# pedalboard.net
KiCad netlist of a schematic drawn in EAGLE
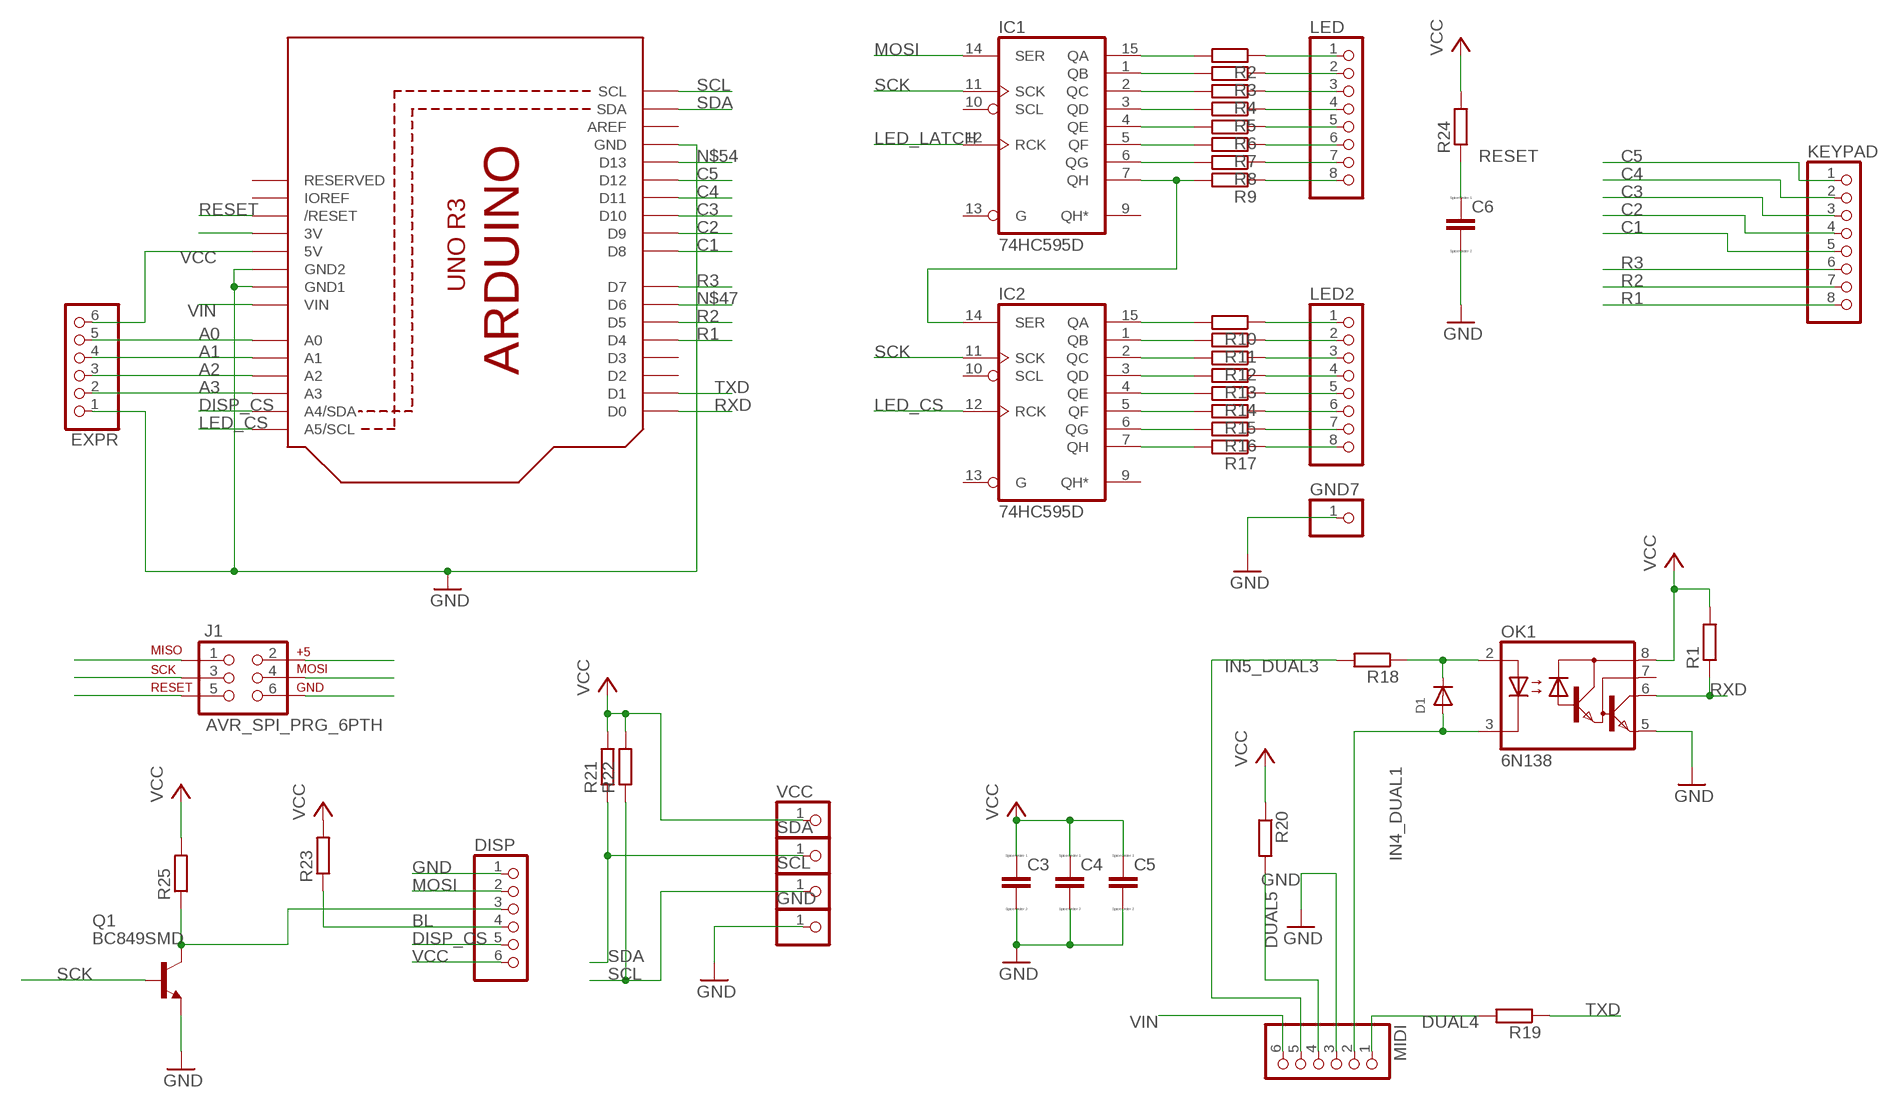
[diagram p0: schematic, sheet 1]

(export (version "E")
  (design (tool "Eeschema 10.0.6"))
  (components
    (comp (ref "C3")
      (value "CC0603")
      (footprint "eagle-import:C0603")
      (libsource (lib "eagle-import") (part "CC0603"))
    )
    (comp (ref "C4")
      (value "CC0603")
      (footprint "eagle-import:C0603")
      (libsource (lib "eagle-import") (part "CC0603"))
    )
    (comp (ref "C5") (value "C") (footprint "eagle-import:C0805") (libsource (lib "eagle-import") (part "C")))
    (comp (ref "C6")
      (value "CC0603")
      (footprint "eagle-import:C0603")
      (libsource (lib "eagle-import") (part "CC0603"))
    )
    (comp (ref "D1")
      (value "DIODEDO-1N4148")
      (footprint "eagle-import:DO-1N4148")
      (libsource (lib "eagle-import") (part "DIODEDO-1N4148"))
    )
    (comp (ref "DISP")
      (value "PINHD-1X6")
      (footprint "eagle-import:1X06")
      (libsource (lib "eagle-import") (part "PINHD-1X6"))
    )
    (comp (ref "EXPR")
      (value "PINHD-1X6")
      (footprint "eagle-import:1X06")
      (libsource (lib "eagle-import") (part "PINHD-1X6"))
    )
    (comp (ref "GND")
      (value "PINHD-1X1")
      (footprint "eagle-import:1X01")
      (libsource (lib "eagle-import") (part "PINHD-1X1"))
    )
    (comp (ref "GND7")
      (value "PINHD-1X1")
      (footprint "eagle-import:1X01")
      (libsource (lib "eagle-import") (part "PINHD-1X1"))
    )
    (comp (ref "IC1")
      (value "74HC595D")
      (footprint "eagle-import:SO16")
      (libsource (lib "eagle-import") (part "74595DHC"))
    )
    (comp (ref "IC2")
      (value "74HC595D")
      (footprint "eagle-import:SO16")
      (libsource (lib "eagle-import") (part "74595DHC"))
    )
    (comp (ref "J1")
      (value "AVR_SPI_PRG_6PTH")
      (footprint "eagle-import:2X3")
      (libsource (lib "eagle-import") (part "AVR_SPI_PRG_6PTH"))
    )
    (comp (ref "KEYPAD")
      (value "PINHD-1X8CLEANBIG")
      (footprint "eagle-import:1X08-CLEANBIG")
      (libsource (lib "eagle-import") (part "PINHD-1X8CLEANBIG"))
    )
    (comp (ref "LED")
      (value "PINHD-1X8CLEANBIG")
      (footprint "eagle-import:1X08-CLEANBIG")
      (libsource (lib "eagle-import") (part "PINHD-1X8CLEANBIG"))
    )
    (comp (ref "LED2")
      (value "PINHD-1X8CLEANBIG")
      (footprint "eagle-import:1X08-CLEANBIG")
      (libsource (lib "eagle-import") (part "PINHD-1X8CLEANBIG"))
    )
    (comp (ref "MIDI")
      (value "PINHD-1X6")
      (footprint "eagle-import:1X06")
      (libsource (lib "eagle-import") (part "PINHD-1X6"))
    )
    (comp (ref "OK1")
      (value "6N138")
      (footprint "eagle-import:DIL08")
      (fields (field (name "MF") "VISHAY/TELEFUNKEN"))
      (libsource (lib "eagle-import") (part "6N138"))
    )
    (comp (ref "Q1")
      (value "BC849SMD")
      (footprint "eagle-import:SOT23-BEC")
      (libsource (lib "eagle-import") (part "BC849SMD"))
    )
    (comp (ref "R1")
      (value "R-EU_R0805")
      (footprint "eagle-import:R0805")
      (libsource (lib "eagle-import") (part "R-EU_R0805"))
    )
    (comp (ref "R2")
      (value "R-EU_R0805")
      (footprint "eagle-import:R0805")
      (libsource (lib "eagle-import") (part "R-EU_R0805"))
    )
    (comp (ref "R3")
      (value "R-EU_R0805")
      (footprint "eagle-import:R0805")
      (libsource (lib "eagle-import") (part "R-EU_R0805"))
    )
    (comp (ref "R4")
      (value "R-EU_R0805")
      (footprint "eagle-import:R0805")
      (libsource (lib "eagle-import") (part "R-EU_R0805"))
    )
    (comp (ref "R5")
      (value "R-EU_R0805")
      (footprint "eagle-import:R0805")
      (libsource (lib "eagle-import") (part "R-EU_R0805"))
    )
    (comp (ref "R6")
      (value "R-EU_R0805")
      (footprint "eagle-import:R0805")
      (libsource (lib "eagle-import") (part "R-EU_R0805"))
    )
    (comp (ref "R7")
      (value "R-EU_R0805")
      (footprint "eagle-import:R0805")
      (libsource (lib "eagle-import") (part "R-EU_R0805"))
    )
    (comp (ref "R8")
      (value "R-EU_R0805")
      (footprint "eagle-import:R0805")
      (libsource (lib "eagle-import") (part "R-EU_R0805"))
    )
    (comp (ref "R9")
      (value "R-EU_R0805")
      (footprint "eagle-import:R0805")
      (libsource (lib "eagle-import") (part "R-EU_R0805"))
    )
    (comp (ref "R10")
      (value "R-EU_R0805")
      (footprint "eagle-import:R0805")
      (libsource (lib "eagle-import") (part "R-EU_R0805"))
    )
    (comp (ref "R11")
      (value "R-EU_R0805")
      (footprint "eagle-import:R0805")
      (libsource (lib "eagle-import") (part "R-EU_R0805"))
    )
    (comp (ref "R12")
      (value "R-EU_R0805")
      (footprint "eagle-import:R0805")
      (libsource (lib "eagle-import") (part "R-EU_R0805"))
    )
    (comp (ref "R13")
      (value "R-EU_R0805")
      (footprint "eagle-import:R0805")
      (libsource (lib "eagle-import") (part "R-EU_R0805"))
    )
    (comp (ref "R14")
      (value "R-EU_R0805")
      (footprint "eagle-import:R0805")
      (libsource (lib "eagle-import") (part "R-EU_R0805"))
    )
    (comp (ref "R15")
      (value "R-EU_R0805")
      (footprint "eagle-import:R0805")
      (libsource (lib "eagle-import") (part "R-EU_R0805"))
    )
    (comp (ref "R16")
      (value "R-EU_R0805")
      (footprint "eagle-import:R0805")
      (libsource (lib "eagle-import") (part "R-EU_R0805"))
    )
    (comp (ref "R17")
      (value "R-EU_R0805")
      (footprint "eagle-import:R0805")
      (libsource (lib "eagle-import") (part "R-EU_R0805"))
    )
    (comp (ref "R18")
      (value "R-EU_R0805")
      (footprint "eagle-import:R0805")
      (libsource (lib "eagle-import") (part "R-EU_R0805"))
    )
    (comp (ref "R19")
      (value "R-EU_R0805")
      (footprint "eagle-import:R0805")
      (libsource (lib "eagle-import") (part "R-EU_R0805"))
    )
    (comp (ref "R20")
      (value "R-EU_R0805")
      (footprint "eagle-import:R0805")
      (libsource (lib "eagle-import") (part "R-EU_R0805"))
    )
    (comp (ref "R21")
      (value "R-EU_R0805")
      (footprint "eagle-import:R0805")
      (libsource (lib "eagle-import") (part "R-EU_R0805"))
    )
    (comp (ref "R22")
      (value "R-EU_R0805")
      (footprint "eagle-import:R0805")
      (libsource (lib "eagle-import") (part "R-EU_R0805"))
    )
    (comp (ref "R23")
      (value "R-EU_R0805")
      (footprint "eagle-import:R0805")
      (libsource (lib "eagle-import") (part "R-EU_R0805"))
    )
    (comp (ref "R24")
      (value "R-EU_R0805")
      (footprint "eagle-import:R0805")
      (libsource (lib "eagle-import") (part "R-EU_R0805"))
    )
    (comp (ref "R25")
      (value "R-EU_R0805")
      (footprint "eagle-import:R0805")
      (libsource (lib "eagle-import") (part "R-EU_R0805"))
    )
    (comp (ref "SCL")
      (value "PINHD-1X1")
      (footprint "eagle-import:1X01")
      (libsource (lib "eagle-import") (part "PINHD-1X1"))
    )
    (comp (ref "SDA")
      (value "PINHD-1X1")
      (footprint "eagle-import:1X01")
      (libsource (lib "eagle-import") (part "PINHD-1X1"))
    )
    (comp (ref "U2")
      (value "ARDUINOR3-BPLACE")
      (footprint "eagle-import:ARDUINOR3-BPLACE")
      (libsource (lib "eagle-import") (part "ARDUINOR3-BPLACE"))
    )
    (comp (ref "VCC")
      (value "PINHD-1X1")
      (footprint "eagle-import:1X01")
      (libsource (lib "eagle-import") (part "PINHD-1X1"))
    )
  )
  (nets
    (net (code "1") (name "/A0") (class "Default")
      (node (ref "EXPR") (pin "5") (pinfunction "5_5") (pintype "passive"))
      (node (ref "U2") (pin "A0") (pinfunction "A0_A0") (pintype "bidirectional"))
    )
    (net (code "2") (name "/A1") (class "Default")
      (node (ref "EXPR") (pin "4") (pinfunction "4_4") (pintype "passive"))
      (node (ref "U2") (pin "A1") (pinfunction "A1_A1") (pintype "bidirectional"))
    )
    (net (code "3") (name "/A2") (class "Default")
      (node (ref "EXPR") (pin "3") (pinfunction "3_3") (pintype "passive"))
      (node (ref "U2") (pin "A2") (pinfunction "A2_A2") (pintype "bidirectional"))
    )
    (net (code "4") (name "/A3") (class "Default")
      (node (ref "EXPR") (pin "2") (pinfunction "2_2") (pintype "passive"))
      (node (ref "U2") (pin "A3") (pinfunction "A3_A3") (pintype "bidirectional"))
    )
    (net (code "5") (name "/BL") (class "Default")
      (node (ref "DISP") (pin "4") (pinfunction "4_4") (pintype "passive"))
      (node (ref "R23") (pin "1") (pinfunction "1_1") (pintype "passive"))
    )
    (net (code "6") (name "/C1") (class "Default")
      (node (ref "KEYPAD") (pin "5") (pinfunction "5_5") (pintype "passive"))
      (node (ref "U2") (pin "D8") (pinfunction "D8_D8") (pintype "bidirectional"))
    )
    (net (code "7") (name "/C2") (class "Default")
      (node (ref "KEYPAD") (pin "4") (pinfunction "4_4") (pintype "passive"))
      (node (ref "U2") (pin "D9") (pinfunction "D9_D9") (pintype "bidirectional"))
    )
    (net (code "8") (name "/C3") (class "Default")
      (node (ref "KEYPAD") (pin "3") (pinfunction "3_3") (pintype "passive"))
      (node (ref "U2") (pin "D10") (pinfunction "D10_D10") (pintype "bidirectional"))
    )
    (net (code "9") (name "/C4") (class "Default")
      (node (ref "KEYPAD") (pin "2") (pinfunction "2_2") (pintype "passive"))
      (node (ref "U2") (pin "D11") (pinfunction "D11_D11") (pintype "bidirectional"))
    )
    (net (code "10") (name "/C5") (class "Default")
      (node (ref "KEYPAD") (pin "1") (pinfunction "1_1") (pintype "passive"))
      (node (ref "U2") (pin "D12") (pinfunction "D12_D12") (pintype "bidirectional"))
    )
    (net (code "11") (name "/DISP_CS") (class "Default")
      (node (ref "DISP") (pin "5") (pinfunction "5_5") (pintype "passive"))
      (node (ref "U2") (pin "A4") (pinfunction "A4/SDA_A4") (pintype "bidirectional"))
    )
    (net (code "12") (name "/DUAL4") (class "Default")
      (node (ref "MIDI") (pin "1") (pinfunction "1_1") (pintype "passive"))
      (node (ref "R19") (pin "2") (pinfunction "2_2") (pintype "passive"))
    )
    (net (code "13") (name "/DUAL5") (class "Default")
      (node (ref "MIDI") (pin "4") (pinfunction "4_4") (pintype "passive"))
      (node (ref "R20") (pin "2") (pinfunction "2_2") (pintype "passive"))
    )
    (net (code "14") (name "/IN4_DUAL1") (class "Default")
      (node (ref "D1") (pin "A") (pinfunction "A_A") (pintype "passive"))
      (node (ref "MIDI") (pin "2") (pinfunction "2_2") (pintype "passive"))
      (node (ref "OK1") (pin "3") (pinfunction "C_3") (pintype "passive"))
    )
    (net (code "15") (name "/IN5_DUAL3") (class "Default")
      (node (ref "MIDI") (pin "5") (pinfunction "5_5") (pintype "passive"))
      (node (ref "R18") (pin "2") (pinfunction "2_2") (pintype "passive"))
    )
    (net (code "16") (name "/LED_CS") (class "Default")
      (node (ref "IC2") (pin "12") (pinfunction "RCK_12") (pintype "input"))
      (node (ref "U2") (pin "A5") (pinfunction "A5/SCL_A5") (pintype "bidirectional"))
    )
    (net (code "17") (name "/LED_LATCH") (class "Default")
      (node (ref "IC1") (pin "12") (pinfunction "RCK_12") (pintype "input"))
    )
    (net (code "18") (name "/MOSI") (class "Default")
      (node (ref "DISP") (pin "2") (pinfunction "2_2") (pintype "passive"))
      (node (ref "IC1") (pin "14") (pinfunction "SER_14") (pintype "input"))
      (node (ref "J1") (pin "4") (pinfunction "4_4") (pintype "passive"))
    )
    (net (code "19") (name "/N$47") (class "Default")
      (node (ref "U2") (pin "D6") (pinfunction "D6_D6") (pintype "bidirectional"))
    )
    (net (code "20") (name "/N$54") (class "Default")
      (node (ref "U2") (pin "D13") (pinfunction "D13_D13") (pintype "bidirectional"))
    )
    (net (code "21") (name "/R1") (class "Default")
      (node (ref "KEYPAD") (pin "8") (pinfunction "8_8") (pintype "passive"))
      (node (ref "U2") (pin "D4") (pinfunction "D4_D4") (pintype "bidirectional"))
    )
    (net (code "22") (name "/R2") (class "Default")
      (node (ref "KEYPAD") (pin "7") (pinfunction "7_7") (pintype "passive"))
      (node (ref "U2") (pin "D5") (pinfunction "D5_D5") (pintype "bidirectional"))
    )
    (net (code "23") (name "/R3") (class "Default")
      (node (ref "KEYPAD") (pin "6") (pinfunction "6_6") (pintype "passive"))
      (node (ref "U2") (pin "D7") (pinfunction "D7_D7") (pintype "bidirectional"))
    )
    (net (code "24") (name "/RESET") (class "Default")
      (node (ref "C6") (pin "1") (pinfunction "1_1") (pintype "passive"))
      (node (ref "J1") (pin "5") (pinfunction "5_5") (pintype "passive"))
      (node (ref "R24") (pin "1") (pinfunction "1_1") (pintype "passive"))
      (node (ref "U2") (pin "RESET") (pinfunction "/RESET_RESET") (pintype "bidirectional"))
    )
    (net (code "25") (name "/RXD") (class "Default")
      (node (ref "OK1") (pin "6") (pinfunction "VO_6") (pintype "passive"))
      (node (ref "R1") (pin "1") (pinfunction "1_1") (pintype "passive"))
      (node (ref "U2") (pin "D0") (pinfunction "D0_D0") (pintype "bidirectional"))
    )
    (net (code "26") (name "/SCK") (class "Default")
      (node (ref "IC1") (pin "11") (pinfunction "SCK_11") (pintype "input"))
      (node (ref "IC2") (pin "11") (pinfunction "SCK_11") (pintype "input"))
      (node (ref "J1") (pin "3") (pinfunction "3_3") (pintype "passive"))
      (node (ref "Q1") (pin "B") (pinfunction "B_B") (pintype "passive"))
    )
    (net (code "27") (name "/SCL") (class "Default")
      (node (ref "R22") (pin "1") (pinfunction "1_1") (pintype "passive"))
      (node (ref "SCL") (pin "1") (pinfunction "1_1") (pintype "passive"))
      (node (ref "U2") (pin "SCL") (pinfunction "SCL_SCL") (pintype "bidirectional"))
    )
    (net (code "28") (name "/SDA") (class "Default")
      (node (ref "R21") (pin "1") (pinfunction "1_1") (pintype "passive"))
      (node (ref "SDA") (pin "1") (pinfunction "1_1") (pintype "passive"))
      (node (ref "U2") (pin "SDA") (pinfunction "SDA_SDA") (pintype "bidirectional"))
    )
    (net (code "29") (name "/TXD") (class "Default")
      (node (ref "R19") (pin "1") (pinfunction "1_1") (pintype "passive"))
      (node (ref "U2") (pin "D1") (pinfunction "D1_D1") (pintype "bidirectional"))
    )
    (net (code "30") (name "/VIN") (class "Default")
      (node (ref "MIDI") (pin "6") (pinfunction "6_6") (pintype "passive"))
      (node (ref "U2") (pin "VIN") (pinfunction "VIN_VIN") (pintype "power_in"))
    )
    (net (code "31") (name "GND") (class "Default")
      (node (ref "C3") (pin "2") (pinfunction "2_2") (pintype "passive"))
      (node (ref "C4") (pin "2") (pinfunction "2_2") (pintype "passive"))
      (node (ref "C5") (pin "2") (pinfunction "2_2") (pintype "passive"))
      (node (ref "C6") (pin "2") (pinfunction "2_2") (pintype "passive"))
      (node (ref "DISP") (pin "1") (pinfunction "1_1") (pintype "passive"))
      (node (ref "EXPR") (pin "1") (pinfunction "1_1") (pintype "passive"))
      (node (ref "GND") (pin "1") (pinfunction "1_1") (pintype "passive"))
      (node (ref "GND7") (pin "1") (pinfunction "1_1") (pintype "passive"))
      (node (ref "J1") (pin "6") (pinfunction "6_6") (pintype "passive"))
      (node (ref "MIDI") (pin "3") (pinfunction "3_3") (pintype "passive"))
      (node (ref "OK1") (pin "5") (pinfunction "GND_5") (pintype "passive"))
      (node (ref "Q1") (pin "E") (pinfunction "E_E") (pintype "passive"))
      (node (ref "U2") (pin "GND") (pinfunction "GND_GND") (pintype "power_in"))
      (node (ref "U2") (pin "GND1") (pinfunction "GND1_GND1") (pintype "power_in"))
      (node (ref "U2") (pin "GND2") (pinfunction "GND2_GND2") (pintype "power_in"))
    )
    (net (code "32") (name "Net-(DISP-Pad3)") (class "Default")
      (node (ref "DISP") (pin "3") (pinfunction "3_3") (pintype "passive"))
      (node (ref "Q1") (pin "C") (pinfunction "C_C") (pintype "passive"))
      (node (ref "R25") (pin "1") (pinfunction "1_1") (pintype "passive"))
    )
    (net (code "33") (name "Net-(IC1A-QA)") (class "Default")
      (node (ref "IC1") (pin "15") (pinfunction "QA_15") (pintype "tri_state"))
      (node (ref "R2") (pin "2") (pinfunction "2_2") (pintype "passive"))
    )
    (net (code "34") (name "Net-(IC1A-QB)") (class "Default")
      (node (ref "IC1") (pin "1") (pinfunction "QB_1") (pintype "tri_state"))
      (node (ref "R3") (pin "2") (pinfunction "2_2") (pintype "passive"))
    )
    (net (code "35") (name "Net-(IC1A-QC)") (class "Default")
      (node (ref "IC1") (pin "2") (pinfunction "QC_2") (pintype "tri_state"))
      (node (ref "R4") (pin "2") (pinfunction "2_2") (pintype "passive"))
    )
    (net (code "36") (name "Net-(IC1A-QD)") (class "Default")
      (node (ref "IC1") (pin "3") (pinfunction "QD_3") (pintype "tri_state"))
      (node (ref "R5") (pin "2") (pinfunction "2_2") (pintype "passive"))
    )
    (net (code "37") (name "Net-(IC1A-QE)") (class "Default")
      (node (ref "IC1") (pin "4") (pinfunction "QE_4") (pintype "tri_state"))
      (node (ref "R6") (pin "2") (pinfunction "2_2") (pintype "passive"))
    )
    (net (code "38") (name "Net-(IC1A-QF)") (class "Default")
      (node (ref "IC1") (pin "5") (pinfunction "QF_5") (pintype "tri_state"))
      (node (ref "R7") (pin "2") (pinfunction "2_2") (pintype "passive"))
    )
    (net (code "39") (name "Net-(IC1A-QG)") (class "Default")
      (node (ref "IC1") (pin "6") (pinfunction "QG_6") (pintype "tri_state"))
      (node (ref "R8") (pin "2") (pinfunction "2_2") (pintype "passive"))
    )
    (net (code "40") (name "Net-(IC1A-QH)") (class "Default")
      (node (ref "IC1") (pin "7") (pinfunction "QH_7") (pintype "tri_state"))
      (node (ref "IC2") (pin "14") (pinfunction "SER_14") (pintype "input"))
      (node (ref "R9") (pin "2") (pinfunction "2_2") (pintype "passive"))
    )
    (net (code "41") (name "Net-(IC2A-QA)") (class "Default")
      (node (ref "IC2") (pin "15") (pinfunction "QA_15") (pintype "tri_state"))
      (node (ref "R10") (pin "2") (pinfunction "2_2") (pintype "passive"))
    )
    (net (code "42") (name "Net-(IC2A-QB)") (class "Default")
      (node (ref "IC2") (pin "1") (pinfunction "QB_1") (pintype "tri_state"))
      (node (ref "R11") (pin "2") (pinfunction "2_2") (pintype "passive"))
    )
    (net (code "43") (name "Net-(IC2A-QC)") (class "Default")
      (node (ref "IC2") (pin "2") (pinfunction "QC_2") (pintype "tri_state"))
      (node (ref "R12") (pin "2") (pinfunction "2_2") (pintype "passive"))
    )
    (net (code "44") (name "Net-(IC2A-QD)") (class "Default")
      (node (ref "IC2") (pin "3") (pinfunction "QD_3") (pintype "tri_state"))
      (node (ref "R13") (pin "2") (pinfunction "2_2") (pintype "passive"))
    )
    (net (code "45") (name "Net-(IC2A-QE)") (class "Default")
      (node (ref "IC2") (pin "4") (pinfunction "QE_4") (pintype "tri_state"))
      (node (ref "R14") (pin "2") (pinfunction "2_2") (pintype "passive"))
    )
    (net (code "46") (name "Net-(IC2A-QF)") (class "Default")
      (node (ref "IC2") (pin "5") (pinfunction "QF_5") (pintype "tri_state"))
      (node (ref "R15") (pin "2") (pinfunction "2_2") (pintype "passive"))
    )
    (net (code "47") (name "Net-(IC2A-QG)") (class "Default")
      (node (ref "IC2") (pin "6") (pinfunction "QG_6") (pintype "tri_state"))
      (node (ref "R16") (pin "2") (pinfunction "2_2") (pintype "passive"))
    )
    (net (code "48") (name "Net-(IC2A-QH)") (class "Default")
      (node (ref "IC2") (pin "7") (pinfunction "QH_7") (pintype "tri_state"))
      (node (ref "R17") (pin "2") (pinfunction "2_2") (pintype "passive"))
    )
    (net (code "49") (name "Net-(LED-Pad1)") (class "Default")
      (node (ref "LED") (pin "1") (pinfunction "1_1") (pintype "passive"))
      (node (ref "R2") (pin "1") (pinfunction "1_1") (pintype "passive"))
    )
    (net (code "50") (name "Net-(LED-Pad2)") (class "Default")
      (node (ref "LED") (pin "2") (pinfunction "2_2") (pintype "passive"))
      (node (ref "R3") (pin "1") (pinfunction "1_1") (pintype "passive"))
    )
    (net (code "51") (name "Net-(LED-Pad3)") (class "Default")
      (node (ref "LED") (pin "3") (pinfunction "3_3") (pintype "passive"))
      (node (ref "R4") (pin "1") (pinfunction "1_1") (pintype "passive"))
    )
    (net (code "52") (name "Net-(LED-Pad4)") (class "Default")
      (node (ref "LED") (pin "4") (pinfunction "4_4") (pintype "passive"))
      (node (ref "R5") (pin "1") (pinfunction "1_1") (pintype "passive"))
    )
    (net (code "53") (name "Net-(LED-Pad5)") (class "Default")
      (node (ref "LED") (pin "5") (pinfunction "5_5") (pintype "passive"))
      (node (ref "R6") (pin "1") (pinfunction "1_1") (pintype "passive"))
    )
    (net (code "54") (name "Net-(LED-Pad6)") (class "Default")
      (node (ref "LED") (pin "6") (pinfunction "6_6") (pintype "passive"))
      (node (ref "R7") (pin "1") (pinfunction "1_1") (pintype "passive"))
    )
    (net (code "55") (name "Net-(LED-Pad7)") (class "Default")
      (node (ref "LED") (pin "7") (pinfunction "7_7") (pintype "passive"))
      (node (ref "R8") (pin "1") (pinfunction "1_1") (pintype "passive"))
    )
    (net (code "56") (name "Net-(LED-Pad8)") (class "Default")
      (node (ref "LED") (pin "8") (pinfunction "8_8") (pintype "passive"))
      (node (ref "R9") (pin "1") (pinfunction "1_1") (pintype "passive"))
    )
    (net (code "57") (name "Net-(LED2-Pad1)") (class "Default")
      (node (ref "LED2") (pin "1") (pinfunction "1_1") (pintype "passive"))
      (node (ref "R10") (pin "1") (pinfunction "1_1") (pintype "passive"))
    )
    (net (code "58") (name "Net-(LED2-Pad2)") (class "Default")
      (node (ref "LED2") (pin "2") (pinfunction "2_2") (pintype "passive"))
      (node (ref "R11") (pin "1") (pinfunction "1_1") (pintype "passive"))
    )
    (net (code "59") (name "Net-(LED2-Pad3)") (class "Default")
      (node (ref "LED2") (pin "3") (pinfunction "3_3") (pintype "passive"))
      (node (ref "R12") (pin "1") (pinfunction "1_1") (pintype "passive"))
    )
    (net (code "60") (name "Net-(LED2-Pad4)") (class "Default")
      (node (ref "LED2") (pin "4") (pinfunction "4_4") (pintype "passive"))
      (node (ref "R13") (pin "1") (pinfunction "1_1") (pintype "passive"))
    )
    (net (code "61") (name "Net-(LED2-Pad5)") (class "Default")
      (node (ref "LED2") (pin "5") (pinfunction "5_5") (pintype "passive"))
      (node (ref "R14") (pin "1") (pinfunction "1_1") (pintype "passive"))
    )
    (net (code "62") (name "Net-(LED2-Pad6)") (class "Default")
      (node (ref "LED2") (pin "6") (pinfunction "6_6") (pintype "passive"))
      (node (ref "R15") (pin "1") (pinfunction "1_1") (pintype "passive"))
    )
    (net (code "63") (name "Net-(LED2-Pad7)") (class "Default")
      (node (ref "LED2") (pin "7") (pinfunction "7_7") (pintype "passive"))
      (node (ref "R16") (pin "1") (pinfunction "1_1") (pintype "passive"))
    )
    (net (code "64") (name "Net-(LED2-Pad8)") (class "Default")
      (node (ref "LED2") (pin "8") (pinfunction "8_8") (pintype "passive"))
      (node (ref "R17") (pin "1") (pinfunction "1_1") (pintype "passive"))
    )
    (net (code "65") (name "Net-(OK1-A)") (class "Default")
      (node (ref "D1") (pin "C") (pinfunction "C_C") (pintype "passive"))
      (node (ref "OK1") (pin "2") (pinfunction "A_2") (pintype "passive"))
      (node (ref "R18") (pin "1") (pinfunction "1_1") (pintype "passive"))
    )
    (net (code "66") (name "VCC") (class "Default")
      (node (ref "C3") (pin "1") (pinfunction "1_1") (pintype "passive"))
      (node (ref "C4") (pin "1") (pinfunction "1_1") (pintype "passive"))
      (node (ref "C5") (pin "1") (pinfunction "1_1") (pintype "passive"))
      (node (ref "DISP") (pin "6") (pinfunction "6_6") (pintype "passive"))
      (node (ref "EXPR") (pin "6") (pinfunction "6_6") (pintype "passive"))
      (node (ref "J1") (pin "2") (pinfunction "2_2") (pintype "passive"))
      (node (ref "OK1") (pin "8") (pinfunction "VCC_8") (pintype "passive"))
      (node (ref "R1") (pin "2") (pinfunction "2_2") (pintype "passive"))
      (node (ref "R20") (pin "1") (pinfunction "1_1") (pintype "passive"))
      (node (ref "R21") (pin "2") (pinfunction "2_2") (pintype "passive"))
      (node (ref "R22") (pin "2") (pinfunction "2_2") (pintype "passive"))
      (node (ref "R23") (pin "2") (pinfunction "2_2") (pintype "passive"))
      (node (ref "R24") (pin "2") (pinfunction "2_2") (pintype "passive"))
      (node (ref "R25") (pin "2") (pinfunction "2_2") (pintype "passive"))
      (node (ref "U2") (pin "5V") (pinfunction "5V_5V") (pintype "power_in"))
      (node (ref "VCC") (pin "1") (pinfunction "1_1") (pintype "passive"))
    )
    (net (code "67") (name "unconnected-(IC1A-G-Pad13)") (class "Default")
      (node (ref "IC1") (pin "13") (pinfunction "G_13") (pintype "input"))
    )
    (net (code "68") (name "unconnected-(IC1A-QH*-Pad9)") (class "Default")
      (node (ref "IC1") (pin "9") (pinfunction "QH*_9") (pintype "tri_state"))
    )
    (net (code "69") (name "unconnected-(IC1A-SCL-Pad10)") (class "Default")
      (node (ref "IC1") (pin "10") (pinfunction "SCL_10") (pintype "input"))
    )
    (net (code "70") (name "unconnected-(IC2A-G-Pad13)") (class "Default")
      (node (ref "IC2") (pin "13") (pinfunction "G_13") (pintype "input"))
    )
    (net (code "71") (name "unconnected-(IC2A-QH*-Pad9)") (class "Default")
      (node (ref "IC2") (pin "9") (pinfunction "QH*_9") (pintype "tri_state"))
    )
    (net (code "72") (name "unconnected-(IC2A-SCL-Pad10)") (class "Default")
      (node (ref "IC2") (pin "10") (pinfunction "SCL_10") (pintype "input"))
    )
    (net (code "73") (name "unconnected-(J1-Pad1)") (class "Default")
      (node (ref "J1") (pin "1") (pinfunction "1_1") (pintype "passive"))
    )
    (net (code "74") (name "unconnected-(OK1-VB-Pad7)") (class "Default")
      (node (ref "OK1") (pin "7") (pinfunction "VB_7") (pintype "passive"))
    )
    (net (code "75") (name "unconnected-(U2-Pad3V)") (class "Default")
      (node (ref "U2") (pin "3V") (pinfunction "3V_3V") (pintype "power_in"))
    )
    (net (code "76") (name "unconnected-(U2-PadAREF)") (class "Default")
      (node (ref "U2") (pin "AREF") (pinfunction "AREF_AREF") (pintype "bidirectional"))
    )
    (net (code "77") (name "unconnected-(U2-PadD2)") (class "Default")
      (node (ref "U2") (pin "D2") (pinfunction "D2_D2") (pintype "bidirectional"))
    )
    (net (code "78") (name "unconnected-(U2-PadD3)") (class "Default")
      (node (ref "U2") (pin "D3") (pinfunction "D3_D3") (pintype "bidirectional"))
    )
    (net (code "79") (name "unconnected-(U2-PadIOREF)") (class "Default")
      (node (ref "U2") (pin "IOREF") (pinfunction "IOREF_IOREF") (pintype "output"))
    )
    (net (code "80") (name "unconnected-(U2-PadRESERVED)") (class "Default")
      (node (ref "U2") (pin "RESERVED") (pinfunction "RESERVED_RESERVED") (pintype "no_connect"))
    )
  )
)
